# ASM4002.net
KiCad netlist of a schematic drawn in EAGLE
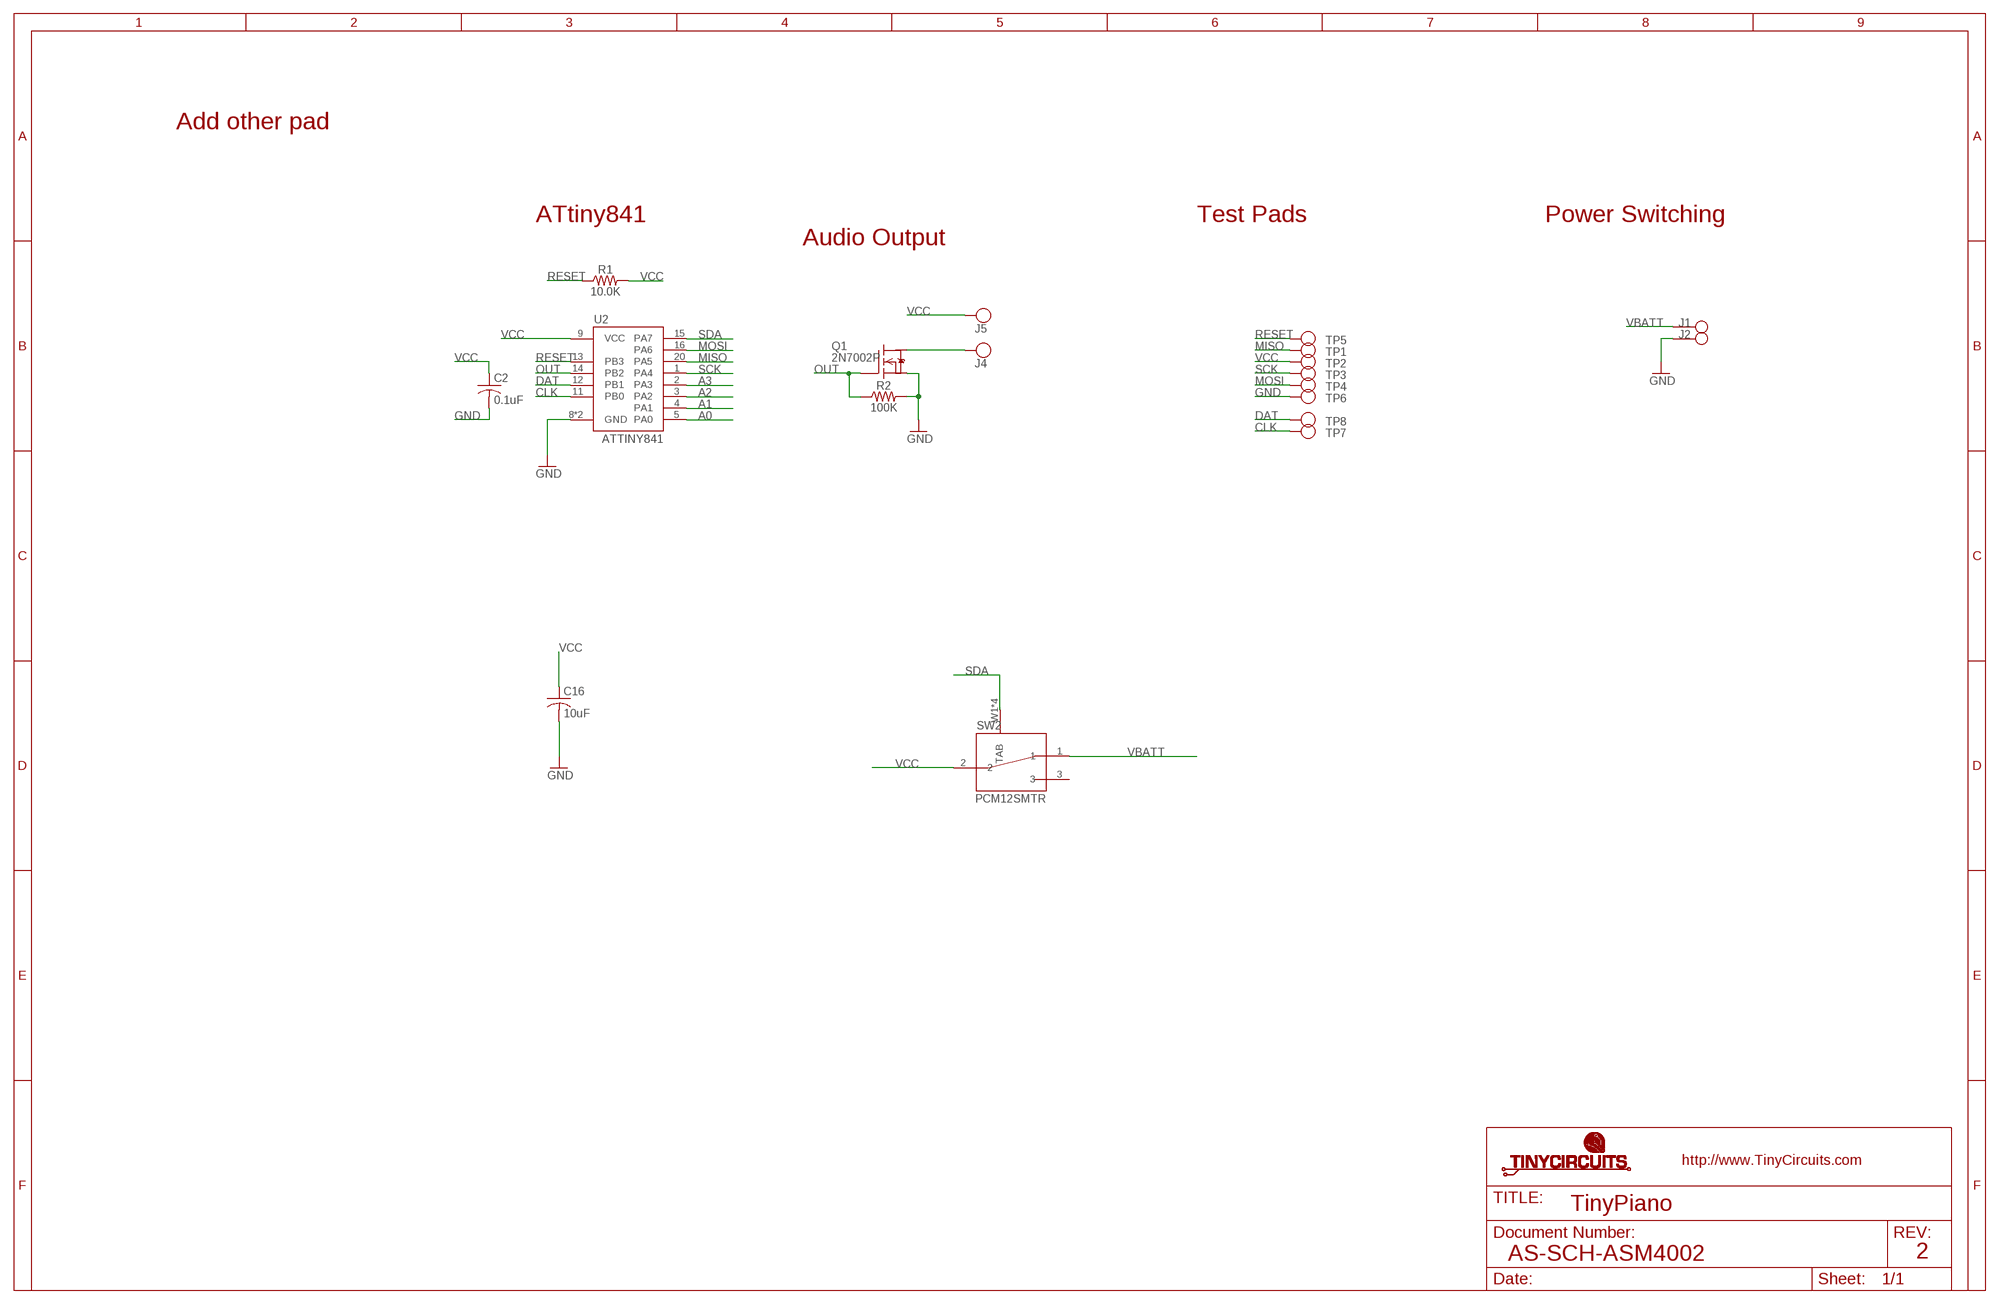
[diagram p0: schematic, sheet 1]

(export (version "E")
  (design (tool "Eeschema 10.0.6"))
  (components
    (comp (ref "C2")
      (value "0.1uF")
      (footprint "eagle-import:C0402")
      (fields (field (name "PARTNO") "AS-ITM-00008"))
      (libsource (lib "eagle-import") (part "AS-ITM-00008"))
    )
    (comp (ref "C16")
      (value "10uF")
      (footprint "eagle-import:C0603")
      (fields (field (name "PARTNO") "AS-ITM-00002") (field (name "PARTNO_1") "AS-ITM-00002"))
      (libsource (lib "eagle-import") (part "AS-ITM-00002"))
    )
    (comp (ref "J1")
      (value "PIN_1X.1\"")
      (footprint "eagle-import:1.4MM_TH")
      (libsource (lib "eagle-import") (part "1.4MM_TH"))
    )
    (comp (ref "J2")
      (value "1.4MM_TH")
      (footprint "eagle-import:1.4MM_TH")
      (libsource (lib "eagle-import") (part "1.4MM_TH"))
    )
    (comp (ref "J4")
      (value "PIN_1X.1\"1")
      (footprint "eagle-import:1X.1__2")
      (libsource (lib "eagle-import") (part "PIN_1X.1{dblquote}1"))
    )
    (comp (ref "J5")
      (value "PIN_1X.1\"1")
      (footprint "eagle-import:1X.1__2")
      (libsource (lib "eagle-import") (part "PIN_1X.1{dblquote}1"))
    )
    (comp (ref "Q1")
      (value "2N7002P")
      (footprint "eagle-import:SOT23A")
      (fields (field (name "PARTNO") "AS-ITM-00007"))
      (libsource (lib "eagle-import") (part "AS-ITM-00007C"))
    )
    (comp (ref "R1")
      (value "10.0K")
      (footprint "eagle-import:0402")
      (fields (field (name "PARTNO") "AS-ITM-00032"))
      (libsource (lib "eagle-import") (part "AS-ITM-00032"))
    )
    (comp (ref "R2")
      (value "100K")
      (footprint "eagle-import:0402")
      (fields (field (name "PARTNO") "AS-ITM-00004"))
      (libsource (lib "eagle-import") (part "AS-ITM-00004"))
    )
    (comp (ref "SW2")
      (value "PCM12SMTR")
      (footprint "eagle-import:PCM12SMTR")
      (fields (field (name "PARTNO") "AS-ITM-00220"))
      (libsource (lib "eagle-import") (part "AS-ITM-00220"))
    )
    (comp (ref "TP1")
      (value "TEST_POINT")
      (footprint "eagle-import:TEST_POINT_1MM")
      (libsource (lib "eagle-import") (part "TEST_POINT"))
    )
    (comp (ref "TP2")
      (value "TEST_POINT")
      (footprint "eagle-import:TEST_POINT_1MM")
      (libsource (lib "eagle-import") (part "TEST_POINT"))
    )
    (comp (ref "TP3")
      (value "TEST_POINT")
      (footprint "eagle-import:TEST_POINT_1MM")
      (libsource (lib "eagle-import") (part "TEST_POINT"))
    )
    (comp (ref "TP4")
      (value "TEST_POINT")
      (footprint "eagle-import:TEST_POINT_1MM")
      (libsource (lib "eagle-import") (part "TEST_POINT"))
    )
    (comp (ref "TP5")
      (value "TEST_POINT")
      (footprint "eagle-import:TEST_POINT_1MM")
      (libsource (lib "eagle-import") (part "TEST_POINT"))
    )
    (comp (ref "TP6")
      (value "TEST_POINT")
      (footprint "eagle-import:TEST_POINT_1MM")
      (libsource (lib "eagle-import") (part "TEST_POINT"))
    )
    (comp (ref "TP7")
      (value "TEST_POINT")
      (footprint "eagle-import:TEST_POINT_1MM")
      (libsource (lib "eagle-import") (part "TEST_POINT"))
    )
    (comp (ref "TP8")
      (value "TEST_POINT")
      (footprint "eagle-import:TEST_POINT_1MM")
      (libsource (lib "eagle-import") (part "TEST_POINT"))
    )
    (comp (ref "U2")
      (value "ATTINY841")
      (footprint "eagle-import:VQFN-20")
      (fields (field (name "PARTNO") "AS-ITM-00255"))
      (libsource (lib "eagle-import") (part "AS-ITM-00255"))
    )
  )
  (nets
    (net (code "1") (name "/A0") (class "Default")
      (node (ref "U2") (pin "5") (pinfunction "PA0_5") (pintype "bidirectional"))
    )
    (net (code "2") (name "/A1") (class "Default")
      (node (ref "U2") (pin "4") (pinfunction "PA1_4") (pintype "bidirectional"))
    )
    (net (code "3") (name "/A2") (class "Default")
      (node (ref "U2") (pin "3") (pinfunction "PA2_3") (pintype "bidirectional"))
    )
    (net (code "4") (name "/A3") (class "Default")
      (node (ref "U2") (pin "2") (pinfunction "PA3_2") (pintype "bidirectional"))
    )
    (net (code "5") (name "/CLK") (class "Default")
      (node (ref "TP7") (pin "P$1") (pinfunction "1_P$1") (pintype "bidirectional"))
      (node (ref "U2") (pin "11") (pinfunction "PB0_11") (pintype "bidirectional"))
    )
    (net (code "6") (name "/DAT") (class "Default")
      (node (ref "TP8") (pin "P$1") (pinfunction "1_P$1") (pintype "bidirectional"))
      (node (ref "U2") (pin "12") (pinfunction "PB1_12") (pintype "bidirectional"))
    )
    (net (code "7") (name "/MISO") (class "Default")
      (node (ref "TP1") (pin "P$1") (pinfunction "1_P$1") (pintype "bidirectional"))
      (node (ref "U2") (pin "20") (pinfunction "PA5_20") (pintype "bidirectional"))
    )
    (net (code "8") (name "/MOSI") (class "Default")
      (node (ref "TP4") (pin "P$1") (pinfunction "1_P$1") (pintype "bidirectional"))
      (node (ref "U2") (pin "16") (pinfunction "PA6_16") (pintype "bidirectional"))
    )
    (net (code "9") (name "/OUT") (class "Default")
      (node (ref "Q1") (pin "B") (pinfunction "G_B") (pintype "passive"))
      (node (ref "R2") (pin "1") (pinfunction "1_1") (pintype "passive"))
      (node (ref "U2") (pin "14") (pinfunction "PB2_14") (pintype "bidirectional"))
    )
    (net (code "10") (name "/RESET") (class "Default")
      (node (ref "R1") (pin "1") (pinfunction "1_1") (pintype "passive"))
      (node (ref "TP5") (pin "P$1") (pinfunction "1_P$1") (pintype "bidirectional"))
      (node (ref "U2") (pin "13") (pinfunction "PB3_13") (pintype "bidirectional"))
    )
    (net (code "11") (name "/SCK") (class "Default")
      (node (ref "TP3") (pin "P$1") (pinfunction "1_P$1") (pintype "bidirectional"))
      (node (ref "U2") (pin "1") (pinfunction "PA4_1") (pintype "bidirectional"))
    )
    (net (code "12") (name "/SDA") (class "Default")
      (node (ref "SW2") (pin "W1") (pinfunction "TAB_W1") (pintype "bidirectional"))
      (node (ref "SW2") (pin "W2") (pinfunction "TAB_W2") (pintype "bidirectional"))
      (node (ref "SW2") (pin "W3") (pinfunction "TAB_W3") (pintype "bidirectional"))
      (node (ref "SW2") (pin "W4") (pinfunction "TAB_W4") (pintype "bidirectional"))
      (node (ref "U2") (pin "15") (pinfunction "PA7_15") (pintype "bidirectional"))
    )
    (net (code "13") (name "/VBATT") (class "Default")
      (node (ref "J1") (pin "P$1") (pinfunction "1_P$1") (pintype "bidirectional"))
      (node (ref "SW2") (pin "1") (pinfunction "1_1") (pintype "bidirectional"))
    )
    (net (code "14") (name "/VCC") (class "Default")
      (node (ref "C16") (pin "1") (pinfunction "1_1") (pintype "passive"))
      (node (ref "C2") (pin "1") (pinfunction "1_1") (pintype "passive"))
      (node (ref "J5") (pin "1") (pinfunction "1_1") (pintype "bidirectional"))
      (node (ref "R1") (pin "2") (pinfunction "2_2") (pintype "passive"))
      (node (ref "SW2") (pin "2") (pinfunction "2_2") (pintype "bidirectional"))
      (node (ref "TP2") (pin "P$1") (pinfunction "1_P$1") (pintype "bidirectional"))
      (node (ref "U2") (pin "9") (pinfunction "VCC_9") (pintype "bidirectional"))
    )
    (net (code "15") (name "GND") (class "Default")
      (node (ref "C16") (pin "2") (pinfunction "2_2") (pintype "passive"))
      (node (ref "C2") (pin "2") (pinfunction "2_2") (pintype "passive"))
      (node (ref "J2") (pin "P$1") (pinfunction "1_P$1") (pintype "bidirectional"))
      (node (ref "Q1") (pin "E") (pinfunction "S_E") (pintype "passive"))
      (node (ref "R2") (pin "2") (pinfunction "2_2") (pintype "passive"))
      (node (ref "TP6") (pin "P$1") (pinfunction "1_P$1") (pintype "bidirectional"))
      (node (ref "U2") (pin "8") (pinfunction "GND_8") (pintype "bidirectional"))
      (node (ref "U2") (pin "PAD") (pinfunction "GND_PAD") (pintype "bidirectional"))
    )
    (net (code "16") (name "Net-(Q1-D)") (class "Default")
      (node (ref "J4") (pin "1") (pinfunction "1_1") (pintype "bidirectional"))
      (node (ref "Q1") (pin "C") (pinfunction "D_C") (pintype "passive"))
    )
    (net (code "17") (name "unconnected-(SW2-Pad3)") (class "Default")
      (node (ref "SW2") (pin "3") (pinfunction "3_3") (pintype "bidirectional"))
    )
  )
)
